# 1Sheeld_PLUS_REV3.net
KiCad netlist of a schematic drawn in EAGLE
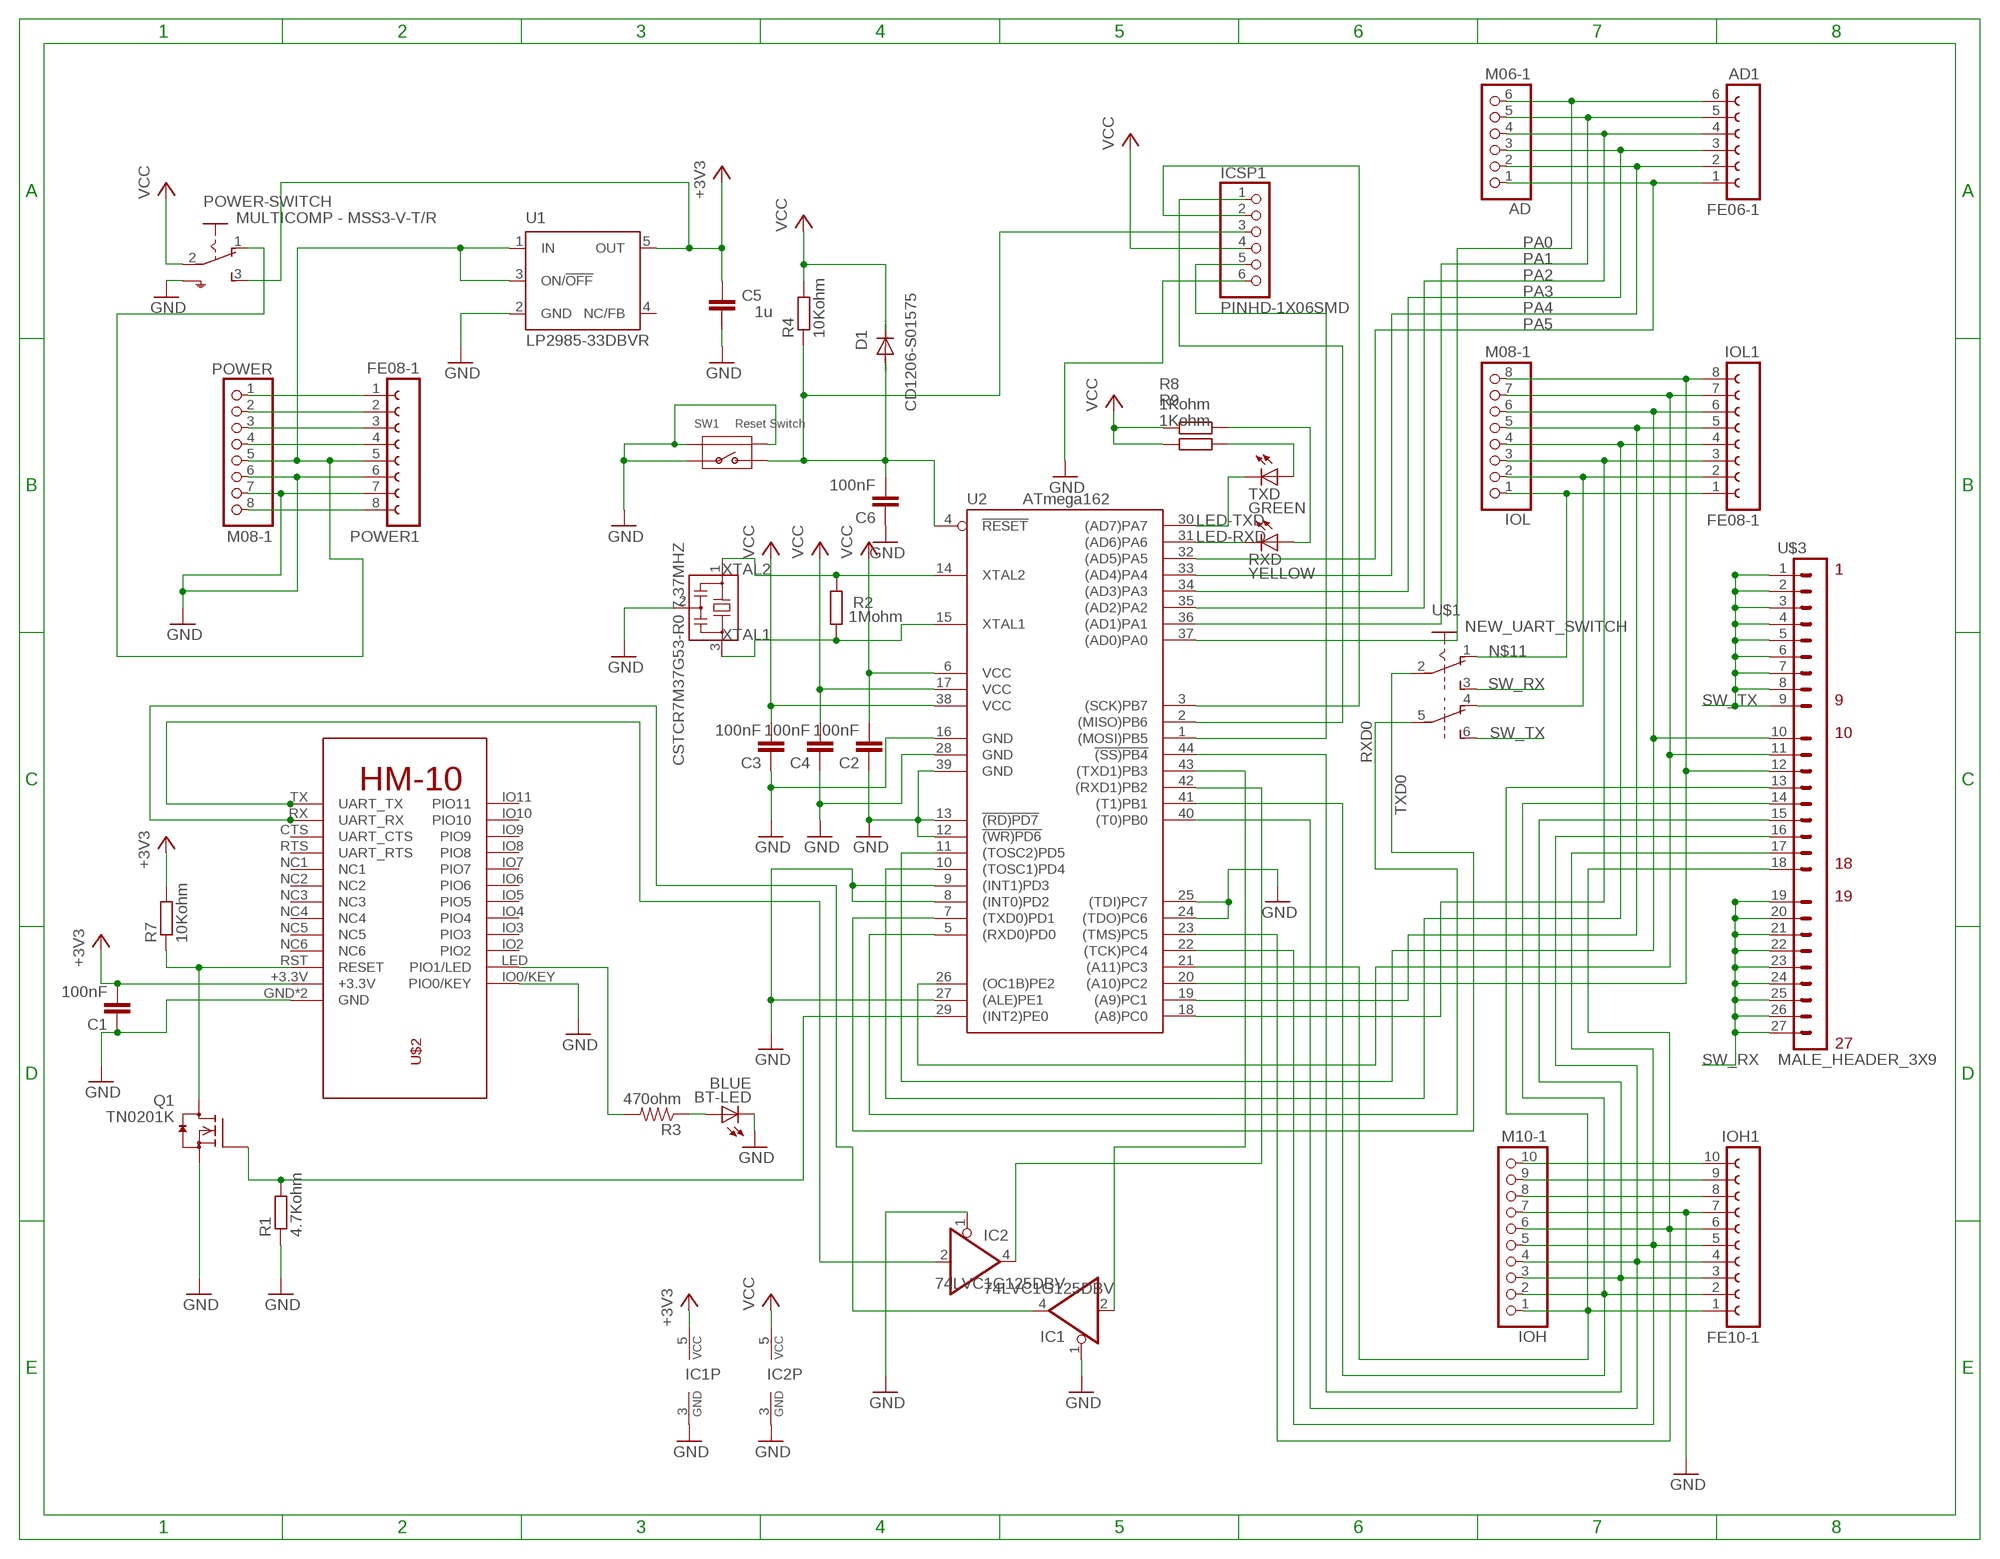
[diagram p0: schematic, sheet 1]

(export (version "E")
  (design (tool "Eeschema 10.0.6"))
  (components
    (comp (ref "AD")
      (value "M06-1")
      (footprint "eagle-import:1X06")
      (libsource (lib "eagle-import") (part "PINHD-1X6"))
    )
    (comp (ref "AD1")
      (value "FE06-1")
      (footprint "eagle-import:FE06")
      (libsource (lib "eagle-import") (part "FE06-1"))
    )
    (comp (ref "BT-LED")
      (value "BLUE")
      (footprint "eagle-import:CHIP-LED0805")
      (libsource (lib "eagle-import") (part "LEDCHIP-LED0805"))
    )
    (comp (ref "C1")
      (value "100nF")
      (footprint "eagle-import:C0603-ROUND")
      (libsource (lib "eagle-import") (part "C-EU0603-RND"))
    )
    (comp (ref "C2")
      (value "100nF")
      (footprint "eagle-import:C0603-ROUND")
      (libsource (lib "eagle-import") (part "C-EU0603-RND"))
    )
    (comp (ref "C3")
      (value "100nF")
      (footprint "eagle-import:C0603-ROUND")
      (libsource (lib "eagle-import") (part "C-EU0603-RND"))
    )
    (comp (ref "C4")
      (value "100nF")
      (footprint "eagle-import:C0603-ROUND")
      (libsource (lib "eagle-import") (part "C-EU0603-RND"))
    )
    (comp (ref "C5")
      (value "1u")
      (footprint "eagle-import:C0603-ROUND")
      (libsource (lib "eagle-import") (part "C-EU0603-RND"))
    )
    (comp (ref "C6")
      (value "100nF")
      (footprint "eagle-import:C0603-ROUND")
      (libsource (lib "eagle-import") (part "C-EU0603-RND"))
    )
    (comp (ref "D1")
      (value "CD1206-S01575")
      (footprint "eagle-import:MINIMELF")
      (libsource (lib "eagle-import") (part "DIODE-MINIMELF"))
    )
    (comp (ref "IC1")
      (value "74LVC1G125DBV")
      (footprint "eagle-import:SOT23-5")
      (libsource (lib "eagle-import") (part "741G125DBVLVC"))
    )
    (comp (ref "IC2")
      (value "74LVC1G125DBV")
      (footprint "eagle-import:SOT23-5")
      (libsource (lib "eagle-import") (part "741G125DBVLVC"))
    )
    (comp (ref "ICSP1")
      (value "PINHD-1X06SMD")
      (footprint "eagle-import:1X06_90SMD")
      (libsource (lib "eagle-import") (part "PINHD-1X06SMD"))
    )
    (comp (ref "IOH")
      (value "M10-1")
      (footprint "eagle-import:1X10")
      (libsource (lib "eagle-import") (part "PINHD-1X10_ARD"))
    )
    (comp (ref "IOH1")
      (value "FE10-1")
      (footprint "eagle-import:FE10")
      (libsource (lib "eagle-import") (part "FE10-1"))
    )
    (comp (ref "IOL")
      (value "M08-1")
      (footprint "eagle-import:1X08")
      (libsource (lib "eagle-import") (part "PINHD-1X8"))
    )
    (comp (ref "IOL1")
      (value "FE08-1")
      (footprint "eagle-import:FE08")
      (libsource (lib "eagle-import") (part "FE08-1"))
    )
    (comp (ref "POWER")
      (value "M08-1")
      (footprint "eagle-import:1X08")
      (libsource (lib "eagle-import") (part "PINHD-1X8"))
    )
    (comp (ref "POWER-SWITCH")
      (value "MULTICOMP - MSS3-V-T/R")
      (footprint "eagle-import:SWITCHMULTI")
      (libsource (lib "eagle-import") (part "SWITCHMULTI"))
    )
    (comp (ref "POWER1")
      (value "FE08-1")
      (footprint "eagle-import:FE08")
      (libsource (lib "eagle-import") (part "FE08-1"))
    )
    (comp (ref "Q1")
      (value "TN0201K")
      (footprint "eagle-import:SOT23")
      (libsource (lib "eagle-import") (part "TN0201K"))
    )
    (comp (ref "R1")
      (value "4.7Kohm")
      (footprint "eagle-import:M0805")
      (libsource (lib "eagle-import") (part "rcl_R-EU_M0805"))
    )
    (comp (ref "R2")
      (value "1Mohm")
      (footprint "eagle-import:R0603-ROUND")
      (libsource (lib "eagle-import") (part "R-EU_R0603"))
    )
    (comp (ref "R3")
      (value "470ohm")
      (footprint "eagle-import:0402-RES")
      (libsource (lib "eagle-import") (part "RESISTOR0402-RES"))
    )
    (comp (ref "R4")
      (value "10Kohm")
      (footprint "eagle-import:M0805")
      (libsource (lib "eagle-import") (part "rcl_R-EU_M0805"))
    )
    (comp (ref "R7")
      (value "10Kohm")
      (footprint "eagle-import:M0805")
      (libsource (lib "eagle-import") (part "rcl_R-EU_M0805"))
    )
    (comp (ref "R8")
      (value "1Kohm")
      (footprint "eagle-import:R0603-ROUND")
      (libsource (lib "eagle-import") (part "R-EU_R0603"))
    )
    (comp (ref "R9")
      (value "1Kohm")
      (footprint "eagle-import:R0603-ROUND")
      (libsource (lib "eagle-import") (part "R-EU_R0603"))
    )
    (comp (ref "RXD")
      (value "YELLOW")
      (footprint "eagle-import:CHIP-LED0805")
      (libsource (lib "eagle-import") (part "LEDCHIP-LED0805"))
    )
    (comp (ref "SW1")
      (value "Reset Switch")
      (footprint "eagle-import:DISCRETE_4P-SMD-7X3.5X3.5H")
      (libsource (lib "eagle-import") (part "DISCRETE_BUTTON-4P-REINFORCETS-1188E"))
    )
    (comp (ref "TXD")
      (value "GREEN")
      (footprint "eagle-import:CHIP-LED0805")
      (libsource (lib "eagle-import") (part "LEDCHIP-LED0805"))
    )
    (comp (ref "U$1")
      (value "NEW_UART_SWITCH")
      (footprint "eagle-import:NEW_UART_SWITCH")
      (libsource (lib "eagle-import") (part "NEW_UART_SWITCH"))
    )
    (comp (ref "U$2")
      (value "HM-10")
      (footprint "eagle-import:HM-10")
      (libsource (lib "eagle-import") (part "HM-10"))
    )
    (comp (ref "U$3")
      (value "MALE_HEADER_3X9")
      (footprint "eagle-import:MALE_HEADER_3X9")
      (libsource (lib "eagle-import") (part "MALE_HEADER_3X9"))
    )
    (comp (ref "U1")
      (value "LP2985-33DBVR")
      (footprint "eagle-import:SOT23-DBV")
      (libsource (lib "eagle-import") (part "LP2985-XXDBVR33"))
    )
    (comp (ref "U2")
      (value "ATmega162")
      (footprint "eagle-import:TQFP44")
      (libsource (lib "eagle-import") (part "ATMEGA162"))
    )
    (comp (ref "Y1")
      (value "CSTCR7M37G53-R0 7.37MHZ")
      (footprint "eagle-import:CSTCR6M")
      (fields (field (name "MPN") "CSTCR6M00G53-R0"))
      (libsource (lib "eagle-import") (part "CSTCR6M00G53Z"))
    )
  )
  (nets
    (net (code "1") (name "+3V3") (class "Default")
      (node (ref "C1") (pin "2") (pinfunction "2_2") (pintype "passive"))
      (node (ref "C5") (pin "2") (pinfunction "2_2") (pintype "passive"))
      (node (ref "IC1") (pin "5") (pinfunction "VCC_5") (pintype "power_in"))
      (node (ref "POWER-SWITCH") (pin "3") (pinfunction "S_3") (pintype "passive"))
      (node (ref "R7") (pin "2") (pinfunction "2_2") (pintype "passive"))
      (node (ref "U$2") (pin "+3.3V") (pinfunction "+3.3V_+3.3V") (pintype "bidirectional"))
      (node (ref "U1") (pin "5") (pinfunction "OUT_5") (pintype "passive"))
    )
    (net (code "2") (name "/LED-RXD") (class "Default")
      (node (ref "RXD") (pin "C") (pinfunction "C_C") (pintype "passive"))
      (node (ref "U2") (pin "31") (pinfunction "(AD6)PA6_31") (pintype "bidirectional"))
    )
    (net (code "3") (name "/LED-TXD") (class "Default")
      (node (ref "TXD") (pin "C") (pinfunction "C_C") (pintype "passive"))
      (node (ref "U2") (pin "30") (pinfunction "(AD7)PA7_30") (pintype "bidirectional"))
    )
    (net (code "4") (name "/N$11") (class "Default")
      (node (ref "IOL") (pin "1") (pinfunction "1_1") (pintype "passive"))
      (node (ref "IOL1") (pin "1") (pinfunction "1_1") (pintype "passive"))
      (node (ref "U$1") (pin "1") (pinfunction "1_1") (pintype "passive"))
    )
    (net (code "5") (name "/PA0") (class "Default")
      (node (ref "AD") (pin "6") (pinfunction "6_6") (pintype "passive"))
      (node (ref "AD1") (pin "6") (pinfunction "6_6") (pintype "passive"))
      (node (ref "U2") (pin "37") (pinfunction "(AD0)PA0_37") (pintype "bidirectional"))
    )
    (net (code "6") (name "/PA1") (class "Default")
      (node (ref "AD") (pin "5") (pinfunction "5_5") (pintype "passive"))
      (node (ref "AD1") (pin "5") (pinfunction "5_5") (pintype "passive"))
      (node (ref "U2") (pin "36") (pinfunction "(AD1)PA1_36") (pintype "bidirectional"))
    )
    (net (code "7") (name "/PA2") (class "Default")
      (node (ref "AD") (pin "4") (pinfunction "4_4") (pintype "passive"))
      (node (ref "AD1") (pin "4") (pinfunction "4_4") (pintype "passive"))
      (node (ref "U2") (pin "35") (pinfunction "(AD2)PA2_35") (pintype "bidirectional"))
    )
    (net (code "8") (name "/PA3") (class "Default")
      (node (ref "AD") (pin "3") (pinfunction "3_3") (pintype "passive"))
      (node (ref "AD1") (pin "3") (pinfunction "3_3") (pintype "passive"))
      (node (ref "U2") (pin "34") (pinfunction "(AD3)PA3_34") (pintype "bidirectional"))
    )
    (net (code "9") (name "/PA4") (class "Default")
      (node (ref "AD") (pin "2") (pinfunction "2_2") (pintype "passive"))
      (node (ref "AD1") (pin "2") (pinfunction "2_2") (pintype "passive"))
      (node (ref "U2") (pin "33") (pinfunction "(AD4)PA4_33") (pintype "bidirectional"))
    )
    (net (code "10") (name "/PA5") (class "Default")
      (node (ref "AD") (pin "1") (pinfunction "1_1") (pintype "passive"))
      (node (ref "AD1") (pin "1") (pinfunction "1_1") (pintype "passive"))
      (node (ref "U2") (pin "32") (pinfunction "(AD5)PA5_32") (pintype "bidirectional"))
    )
    (net (code "11") (name "/RXD0") (class "Default")
      (node (ref "U$1") (pin "5") (pinfunction "5_5") (pintype "passive"))
      (node (ref "U2") (pin "5") (pinfunction "(RXD0)PD0_5") (pintype "bidirectional"))
    )
    (net (code "12") (name "/SW_RX") (class "Default")
      (node (ref "U$1") (pin "3") (pinfunction "3_3") (pintype "passive"))
      (node (ref "U$3") (pin "19") (pinfunction "19_19") (pintype "passive"))
      (node (ref "U$3") (pin "20") (pinfunction "20_20") (pintype "passive"))
      (node (ref "U$3") (pin "21") (pinfunction "21_21") (pintype "passive"))
      (node (ref "U$3") (pin "22") (pinfunction "22_22") (pintype "passive"))
      (node (ref "U$3") (pin "23") (pinfunction "23_23") (pintype "passive"))
      (node (ref "U$3") (pin "24") (pinfunction "24_24") (pintype "passive"))
      (node (ref "U$3") (pin "25") (pinfunction "25_25") (pintype "passive"))
      (node (ref "U$3") (pin "26") (pinfunction "26_26") (pintype "passive"))
      (node (ref "U$3") (pin "27") (pinfunction "27_27") (pintype "passive"))
    )
    (net (code "13") (name "/SW_TX") (class "Default")
      (node (ref "U$1") (pin "6") (pinfunction "6_6") (pintype "passive"))
      (node (ref "U$3") (pin "1") (pinfunction "1_1") (pintype "passive"))
      (node (ref "U$3") (pin "2") (pinfunction "2_2") (pintype "passive"))
      (node (ref "U$3") (pin "3") (pinfunction "3_3") (pintype "passive"))
      (node (ref "U$3") (pin "4") (pinfunction "4_4") (pintype "passive"))
      (node (ref "U$3") (pin "5") (pinfunction "5_5") (pintype "passive"))
      (node (ref "U$3") (pin "6") (pinfunction "6_6") (pintype "passive"))
      (node (ref "U$3") (pin "7") (pinfunction "7_7") (pintype "passive"))
      (node (ref "U$3") (pin "8") (pinfunction "8_8") (pintype "passive"))
      (node (ref "U$3") (pin "9") (pinfunction "9_9") (pintype "passive"))
    )
    (net (code "14") (name "/TXD0") (class "Default")
      (node (ref "U$1") (pin "2") (pinfunction "2_2") (pintype "passive"))
      (node (ref "U2") (pin "7") (pinfunction "(TXD0)PD1_7") (pintype "bidirectional"))
    )
    (net (code "15") (name "/XTAL1") (class "Default")
      (node (ref "R2") (pin "1") (pinfunction "1_1") (pintype "passive"))
      (node (ref "U2") (pin "15") (pinfunction "XTAL1_15") (pintype "input"))
      (node (ref "Y1") (pin "3") (pinfunction "3_3") (pintype "passive"))
    )
    (net (code "16") (name "/XTAL2") (class "Default")
      (node (ref "R2") (pin "2") (pinfunction "2_2") (pintype "passive"))
      (node (ref "U2") (pin "14") (pinfunction "XTAL2_14") (pintype "input"))
      (node (ref "Y1") (pin "1") (pinfunction "1_1") (pintype "passive"))
    )
    (net (code "17") (name "GND") (class "Default")
      (node (ref "BT-LED") (pin "C") (pinfunction "C_C") (pintype "passive"))
      (node (ref "C1") (pin "1") (pinfunction "1_1") (pintype "passive"))
      (node (ref "C2") (pin "1") (pinfunction "1_1") (pintype "passive"))
      (node (ref "C3") (pin "1") (pinfunction "1_1") (pintype "passive"))
      (node (ref "C4") (pin "1") (pinfunction "1_1") (pintype "passive"))
      (node (ref "C5") (pin "1") (pinfunction "1_1") (pintype "passive"))
      (node (ref "C6") (pin "1") (pinfunction "1_1") (pintype "passive"))
      (node (ref "IC1") (pin "1") (pinfunction "OE_1") (pintype "input"))
      (node (ref "IC1") (pin "3") (pinfunction "GND_3") (pintype "power_in"))
      (node (ref "IC2") (pin "1") (pinfunction "OE_1") (pintype "input"))
      (node (ref "IC2") (pin "3") (pinfunction "GND_3") (pintype "power_in"))
      (node (ref "ICSP1") (pin "6") (pinfunction "6_6") (pintype "passive"))
      (node (ref "IOH") (pin "7") (pinfunction "7_7") (pintype "passive"))
      (node (ref "IOH1") (pin "7") (pinfunction "7_7") (pintype "passive"))
      (node (ref "POWER") (pin "6") (pinfunction "6_6") (pintype "passive"))
      (node (ref "POWER") (pin "7") (pinfunction "7_7") (pintype "passive"))
      (node (ref "POWER-SWITCH") (pin "P$4") (pinfunction "SH_P$4") (pintype "passive"))
      (node (ref "POWER-SWITCH") (pin "P$5") (pinfunction "SH_P$5") (pintype "passive"))
      (node (ref "POWER-SWITCH") (pin "P$6") (pinfunction "SH_P$6") (pintype "passive"))
      (node (ref "POWER-SWITCH") (pin "P$7") (pinfunction "SH_P$7") (pintype "passive"))
      (node (ref "POWER1") (pin "6") (pinfunction "6_6") (pintype "passive"))
      (node (ref "POWER1") (pin "7") (pinfunction "7_7") (pintype "passive"))
      (node (ref "Q1") (pin "2") (pinfunction "S_2") (pintype "passive"))
      (node (ref "R1") (pin "1") (pinfunction "1_1") (pintype "passive"))
      (node (ref "SW1") (pin "1") (pinfunction "1_1") (pintype "bidirectional"))
      (node (ref "SW1") (pin "S1") (pinfunction "S1_S1") (pintype "bidirectional"))
      (node (ref "SW1") (pin "S2") (pinfunction "S2_S2") (pintype "bidirectional"))
      (node (ref "U$2") (pin "GND") (pinfunction "GND_GND") (pintype "bidirectional"))
      (node (ref "U$2") (pin "GND2") (pinfunction "GND_GND2") (pintype "bidirectional"))
      (node (ref "U$2") (pin "IO0/KEY") (pinfunction "PIO0/KEY_IO0/KEY") (pintype "bidirectional"))
      (node (ref "U1") (pin "2") (pinfunction "GND_2") (pintype "power_in"))
      (node (ref "U2") (pin "12") (pinfunction "~{(WR})PD6_12") (pintype "bidirectional"))
      (node (ref "U2") (pin "13") (pinfunction "~{(RD})PD7_13") (pintype "bidirectional"))
      (node (ref "U2") (pin "16") (pinfunction "GND_16") (pintype "power_in"))
      (node (ref "U2") (pin "24") (pinfunction "(TDO)PC6_24") (pintype "bidirectional"))
      (node (ref "U2") (pin "25") (pinfunction "(TDI)PC7_25") (pintype "bidirectional"))
      (node (ref "U2") (pin "27") (pinfunction "(ALE)PE1_27") (pintype "bidirectional"))
      (node (ref "U2") (pin "28") (pinfunction "GND_28") (pintype "power_in"))
      (node (ref "U2") (pin "39") (pinfunction "GND_39") (pintype "power_in"))
      (node (ref "U2") (pin "8") (pinfunction "(INT0)PD2_8") (pintype "bidirectional"))
      (node (ref "U2") (pin "9") (pinfunction "(INT1)PD3_9") (pintype "bidirectional"))
      (node (ref "Y1") (pin "2") (pinfunction "2_2") (pintype "passive"))
    )
    (net (code "18") (name "Net-(BT-LED-PadA)") (class "Default")
      (node (ref "BT-LED") (pin "A") (pinfunction "A_A") (pintype "passive"))
      (node (ref "R3") (pin "1") (pinfunction "1_1") (pintype "passive"))
    )
    (net (code "19") (name "Net-(IC1A-I)") (class "Default")
      (node (ref "IC1") (pin "2") (pinfunction "I_2") (pintype "input"))
      (node (ref "U2") (pin "43") (pinfunction "(TXD1)PB3_43") (pintype "bidirectional"))
    )
    (net (code "20") (name "Net-(IC1A-O)") (class "Default")
      (node (ref "IC1") (pin "4") (pinfunction "O_4") (pintype "tri_state"))
      (node (ref "U$2") (pin "RX") (pinfunction "UART_RX_RX") (pintype "bidirectional"))
    )
    (net (code "21") (name "Net-(IC2A-I)") (class "Default")
      (node (ref "IC2") (pin "2") (pinfunction "I_2") (pintype "input"))
      (node (ref "U$2") (pin "TX") (pinfunction "UART_TX_TX") (pintype "bidirectional"))
    )
    (net (code "22") (name "Net-(IC2A-O)") (class "Default")
      (node (ref "IC2") (pin "4") (pinfunction "O_4") (pintype "tri_state"))
      (node (ref "U2") (pin "42") (pinfunction "(RXD1)PB2_42") (pintype "bidirectional"))
    )
    (net (code "23") (name "Net-(IOH-Pad8)") (class "Default")
      (node (ref "IOH") (pin "8") (pinfunction "8_8") (pintype "passive"))
      (node (ref "IOH1") (pin "8") (pinfunction "8_8") (pintype "passive"))
    )
    (net (code "24") (name "Net-(IOH-Pad9)") (class "Default")
      (node (ref "IOH") (pin "9") (pinfunction "9_9") (pintype "passive"))
      (node (ref "IOH1") (pin "9") (pinfunction "9_9") (pintype "passive"))
    )
    (net (code "25") (name "Net-(IOH-Pad10)") (class "Default")
      (node (ref "IOH") (pin "10") (pinfunction "10_10") (pintype "passive"))
      (node (ref "IOH1") (pin "10") (pinfunction "10_10") (pintype "passive"))
    )
    (net (code "26") (name "Net-(IOL-Pad2)") (class "Default")
      (node (ref "IOL") (pin "2") (pinfunction "2_2") (pintype "passive"))
      (node (ref "IOL1") (pin "2") (pinfunction "2_2") (pintype "passive"))
      (node (ref "U$1") (pin "4") (pinfunction "4_4") (pintype "passive"))
    )
    (net (code "27") (name "Net-(POWER-Pad1)") (class "Default")
      (node (ref "POWER") (pin "1") (pinfunction "1_1") (pintype "passive"))
      (node (ref "POWER1") (pin "1") (pinfunction "1_1") (pintype "passive"))
    )
    (net (code "28") (name "Net-(POWER-Pad2)") (class "Default")
      (node (ref "POWER") (pin "2") (pinfunction "2_2") (pintype "passive"))
      (node (ref "POWER1") (pin "2") (pinfunction "2_2") (pintype "passive"))
    )
    (net (code "29") (name "Net-(POWER-Pad3)") (class "Default")
      (node (ref "POWER") (pin "3") (pinfunction "3_3") (pintype "passive"))
      (node (ref "POWER1") (pin "3") (pinfunction "3_3") (pintype "passive"))
    )
    (net (code "30") (name "Net-(POWER-Pad4)") (class "Default")
      (node (ref "POWER") (pin "4") (pinfunction "4_4") (pintype "passive"))
      (node (ref "POWER1") (pin "4") (pinfunction "4_4") (pintype "passive"))
    )
    (net (code "31") (name "Net-(POWER-Pad8)") (class "Default")
      (node (ref "POWER") (pin "8") (pinfunction "8_8") (pintype "passive"))
      (node (ref "POWER1") (pin "8") (pinfunction "8_8") (pintype "passive"))
    )
    (net (code "32") (name "Net-(POWER-SWITCH-O)") (class "Default")
      (node (ref "POWER") (pin "5") (pinfunction "5_5") (pintype "passive"))
      (node (ref "POWER-SWITCH") (pin "1") (pinfunction "O_1") (pintype "passive"))
      (node (ref "POWER1") (pin "5") (pinfunction "5_5") (pintype "passive"))
      (node (ref "U1") (pin "1") (pinfunction "IN_1") (pintype "input"))
      (node (ref "U1") (pin "3") (pinfunction "ON/~{OFF}_3") (pintype "input"))
    )
    (net (code "33") (name "Net-(Q1-D)") (class "Default")
      (node (ref "Q1") (pin "3") (pinfunction "D_3") (pintype "passive"))
      (node (ref "R7") (pin "1") (pinfunction "1_1") (pintype "passive"))
      (node (ref "U$2") (pin "RST") (pinfunction "RESET_RST") (pintype "bidirectional"))
    )
    (net (code "34") (name "Net-(Q1-G)") (class "Default")
      (node (ref "Q1") (pin "1") (pinfunction "G_1") (pintype "passive"))
      (node (ref "R1") (pin "2") (pinfunction "2_2") (pintype "passive"))
      (node (ref "U2") (pin "29") (pinfunction "(INT2)PE0_29") (pintype "bidirectional"))
    )
    (net (code "35") (name "Net-(R8-Pad1)") (class "Default")
      (node (ref "R8") (pin "1") (pinfunction "1_1") (pintype "passive"))
      (node (ref "RXD") (pin "A") (pinfunction "A_A") (pintype "passive"))
    )
    (net (code "36") (name "Net-(R9-Pad1)") (class "Default")
      (node (ref "R9") (pin "1") (pinfunction "1_1") (pintype "passive"))
      (node (ref "TXD") (pin "A") (pinfunction "A_A") (pintype "passive"))
    )
    (net (code "37") (name "Net-(U$2-PIO1{slash}LED)") (class "Default")
      (node (ref "R3") (pin "2") (pinfunction "2_2") (pintype "passive"))
      (node (ref "U$2") (pin "LED") (pinfunction "PIO1/LED_LED") (pintype "bidirectional"))
    )
    (net (code "38") (name "Net-(U2-(A8)PC0)") (class "Default")
      (node (ref "IOL") (pin "3") (pinfunction "3_3") (pintype "passive"))
      (node (ref "IOL1") (pin "3") (pinfunction "3_3") (pintype "passive"))
      (node (ref "U2") (pin "18") (pinfunction "(A8)PC0_18") (pintype "bidirectional"))
    )
    (net (code "39") (name "Net-(U2-(A9)PC1)") (class "Default")
      (node (ref "IOL") (pin "5") (pinfunction "5_5") (pintype "passive"))
      (node (ref "IOL1") (pin "5") (pinfunction "5_5") (pintype "passive"))
      (node (ref "U2") (pin "19") (pinfunction "(A9)PC1_19") (pintype "bidirectional"))
    )
    (net (code "40") (name "Net-(U2-(A10)PC2)") (class "Default")
      (node (ref "IOL") (pin "8") (pinfunction "8_8") (pintype "passive"))
      (node (ref "IOL1") (pin "8") (pinfunction "8_8") (pintype "passive"))
      (node (ref "U$3") (pin "12") (pinfunction "12_12") (pintype "passive"))
      (node (ref "U2") (pin "20") (pinfunction "(A10)PC2_20") (pintype "bidirectional"))
    )
    (net (code "41") (name "Net-(U2-(A11)PC3)") (class "Default")
      (node (ref "IOH") (pin "1") (pinfunction "1_1") (pintype "passive"))
      (node (ref "IOH1") (pin "1") (pinfunction "1_1") (pintype "passive"))
      (node (ref "U$3") (pin "13") (pinfunction "13_13") (pintype "passive"))
      (node (ref "U2") (pin "21") (pinfunction "(A11)PC3_21") (pintype "bidirectional"))
    )
    (net (code "42") (name "Net-(U2-(MISO)PB6)") (class "Default")
      (node (ref "ICSP1") (pin "1") (pinfunction "1_1") (pintype "passive"))
      (node (ref "U2") (pin "2") (pinfunction "(MISO)PB6_2") (pintype "bidirectional"))
    )
    (net (code "43") (name "Net-(U2-(MOSI)PB5)") (class "Default")
      (node (ref "ICSP1") (pin "5") (pinfunction "5_5") (pintype "passive"))
      (node (ref "U2") (pin "1") (pinfunction "(MOSI)PB5_1") (pintype "bidirectional"))
    )
    (net (code "44") (name "Net-(U2-(OC1B)PE2)") (class "Default")
      (node (ref "IOL") (pin "7") (pinfunction "7_7") (pintype "passive"))
      (node (ref "IOL1") (pin "7") (pinfunction "7_7") (pintype "passive"))
      (node (ref "U$3") (pin "11") (pinfunction "11_11") (pintype "passive"))
      (node (ref "U2") (pin "26") (pinfunction "(OC1B)PE2_26") (pintype "bidirectional"))
    )
    (net (code "45") (name "Net-(U2-(SCK)PB7)") (class "Default")
      (node (ref "ICSP1") (pin "2") (pinfunction "2_2") (pintype "passive"))
      (node (ref "U2") (pin "3") (pinfunction "(SCK)PB7_3") (pintype "bidirectional"))
    )
    (net (code "46") (name "Net-(U2-(T0)PB0)") (class "Default")
      (node (ref "IOH") (pin "4") (pinfunction "4_4") (pintype "passive"))
      (node (ref "IOH1") (pin "4") (pinfunction "4_4") (pintype "passive"))
      (node (ref "U$3") (pin "16") (pinfunction "16_16") (pintype "passive"))
      (node (ref "U2") (pin "40") (pinfunction "(T0)PB0_40") (pintype "bidirectional"))
    )
    (net (code "47") (name "Net-(U2-(T1)PB1)") (class "Default")
      (node (ref "IOH") (pin "2") (pinfunction "2_2") (pintype "passive"))
      (node (ref "IOH1") (pin "2") (pinfunction "2_2") (pintype "passive"))
      (node (ref "U$3") (pin "14") (pinfunction "14_14") (pintype "passive"))
      (node (ref "U2") (pin "41") (pinfunction "(T1)PB1_41") (pintype "bidirectional"))
    )
    (net (code "48") (name "Net-(U2-(TCK)PC4)") (class "Default")
      (node (ref "IOH") (pin "5") (pinfunction "5_5") (pintype "passive"))
      (node (ref "IOH1") (pin "5") (pinfunction "5_5") (pintype "passive"))
      (node (ref "U$3") (pin "17") (pinfunction "17_17") (pintype "passive"))
      (node (ref "U2") (pin "22") (pinfunction "(TCK)PC4_22") (pintype "bidirectional"))
    )
    (net (code "49") (name "Net-(U2-(TMS)PC5)") (class "Default")
      (node (ref "IOH") (pin "6") (pinfunction "6_6") (pintype "passive"))
      (node (ref "IOH1") (pin "6") (pinfunction "6_6") (pintype "passive"))
      (node (ref "U$3") (pin "18") (pinfunction "18_18") (pintype "passive"))
      (node (ref "U2") (pin "23") (pinfunction "(TMS)PC5_23") (pintype "bidirectional"))
    )
    (net (code "50") (name "Net-(U2-(TOSC1)PD4)") (class "Default")
      (node (ref "IOL") (pin "4") (pinfunction "4_4") (pintype "passive"))
      (node (ref "IOL1") (pin "4") (pinfunction "4_4") (pintype "passive"))
      (node (ref "U2") (pin "10") (pinfunction "(TOSC1)PD4_10") (pintype "bidirectional"))
    )
    (net (code "51") (name "Net-(U2-(TOSC2)PD5)") (class "Default")
      (node (ref "IOL") (pin "6") (pinfunction "6_6") (pintype "passive"))
      (node (ref "IOL1") (pin "6") (pinfunction "6_6") (pintype "passive"))
      (node (ref "U$3") (pin "10") (pinfunction "10_10") (pintype "passive"))
      (node (ref "U2") (pin "11") (pinfunction "(TOSC2)PD5_11") (pintype "bidirectional"))
    )
    (net (code "52") (name "Net-(U2-~{(SS})PB4)") (class "Default")
      (node (ref "IOH") (pin "3") (pinfunction "3_3") (pintype "passive"))
      (node (ref "IOH1") (pin "3") (pinfunction "3_3") (pintype "passive"))
      (node (ref "U$3") (pin "15") (pinfunction "15_15") (pintype "passive"))
      (node (ref "U2") (pin "44") (pinfunction "~{(SS})PB4_44") (pintype "bidirectional"))
    )
    (net (code "53") (name "Net-(U2-~{RESET})") (class "Default")
      (node (ref "C6") (pin "2") (pinfunction "2_2") (pintype "passive"))
      (node (ref "D1") (pin "A") (pinfunction "A_A") (pintype "passive"))
      (node (ref "ICSP1") (pin "3") (pinfunction "3_3") (pintype "passive"))
      (node (ref "R4") (pin "1") (pinfunction "1_1") (pintype "passive"))
      (node (ref "SW1") (pin "2") (pinfunction "2_2") (pintype "bidirectional"))
      (node (ref "U2") (pin "4") (pinfunction "~{RESET}_4") (pintype "input"))
    )
    (net (code "54") (name "VCC") (class "Default")
      (node (ref "C2") (pin "2") (pinfunction "2_2") (pintype "passive"))
      (node (ref "C3") (pin "2") (pinfunction "2_2") (pintype "passive"))
      (node (ref "C4") (pin "2") (pinfunction "2_2") (pintype "passive"))
      (node (ref "D1") (pin "C") (pinfunction "C_C") (pintype "passive"))
      (node (ref "IC2") (pin "5") (pinfunction "VCC_5") (pintype "power_in"))
      (node (ref "ICSP1") (pin "4") (pinfunction "4_4") (pintype "passive"))
      (node (ref "POWER-SWITCH") (pin "2") (pinfunction "P_2") (pintype "passive"))
      (node (ref "R4") (pin "2") (pinfunction "2_2") (pintype "passive"))
      (node (ref "R8") (pin "2") (pinfunction "2_2") (pintype "passive"))
      (node (ref "R9") (pin "2") (pinfunction "2_2") (pintype "passive"))
      (node (ref "U2") (pin "17") (pinfunction "VCC_17") (pintype "power_in"))
      (node (ref "U2") (pin "38") (pinfunction "VCC_38") (pintype "power_in"))
      (node (ref "U2") (pin "6") (pinfunction "VCC_6") (pintype "power_in"))
    )
    (net (code "55") (name "unconnected-(U$2-PIO2-PadIO2)") (class "Default")
      (node (ref "U$2") (pin "IO2") (pinfunction "PIO2_IO2") (pintype "bidirectional"))
    )
    (net (code "56") (name "unconnected-(U$2-PIO3-PadIO3)") (class "Default")
      (node (ref "U$2") (pin "IO3") (pinfunction "PIO3_IO3") (pintype "bidirectional"))
    )
    (net (code "57") (name "unconnected-(U$2-PIO4-PadIO4)") (class "Default")
      (node (ref "U$2") (pin "IO4") (pinfunction "PIO4_IO4") (pintype "bidirectional"))
    )
    (net (code "58") (name "unconnected-(U$2-PIO5-PadIO5)") (class "Default")
      (node (ref "U$2") (pin "IO5") (pinfunction "PIO5_IO5") (pintype "bidirectional"))
    )
    (net (code "59") (name "unconnected-(U$2-PIO6-PadIO6)") (class "Default")
      (node (ref "U$2") (pin "IO6") (pinfunction "PIO6_IO6") (pintype "bidirectional"))
    )
    (net (code "60") (name "unconnected-(U$2-PIO7-PadIO7)") (class "Default")
      (node (ref "U$2") (pin "IO7") (pinfunction "PIO7_IO7") (pintype "bidirectional"))
    )
    (net (code "61") (name "unconnected-(U$2-PIO8-PadIO8)") (class "Default")
      (node (ref "U$2") (pin "IO8") (pinfunction "PIO8_IO8") (pintype "bidirectional"))
    )
    (net (code "62") (name "unconnected-(U$2-PIO9-PadIO9)") (class "Default")
      (node (ref "U$2") (pin "IO9") (pinfunction "PIO9_IO9") (pintype "bidirectional"))
    )
    (net (code "63") (name "unconnected-(U$2-PIO10-PadIO10)") (class "Default")
      (node (ref "U$2") (pin "IO10") (pinfunction "PIO10_IO10") (pintype "bidirectional"))
    )
    (net (code "64") (name "unconnected-(U$2-PIO11-PadIO11)") (class "Default")
      (node (ref "U$2") (pin "IO11") (pinfunction "PIO11_IO11") (pintype "bidirectional"))
    )
    (net (code "65") (name "unconnected-(U$2-PadNC1)") (class "Default")
      (node (ref "U$2") (pin "NC1") (pinfunction "NC1_NC1") (pintype "bidirectional"))
    )
    (net (code "66") (name "unconnected-(U$2-PadNC2)") (class "Default")
      (node (ref "U$2") (pin "NC2") (pinfunction "NC2_NC2") (pintype "bidirectional"))
    )
    (net (code "67") (name "unconnected-(U$2-PadNC3)") (class "Default")
      (node (ref "U$2") (pin "NC3") (pinfunction "NC3_NC3") (pintype "bidirectional"))
    )
    (net (code "68") (name "unconnected-(U$2-PadNC4)") (class "Default")
      (node (ref "U$2") (pin "NC4") (pinfunction "NC4_NC4") (pintype "bidirectional"))
    )
    (net (code "69") (name "unconnected-(U$2-PadNC5)") (class "Default")
      (node (ref "U$2") (pin "NC5") (pinfunction "NC5_NC5") (pintype "bidirectional"))
    )
    (net (code "70") (name "unconnected-(U$2-PadNC6)") (class "Default")
      (node (ref "U$2") (pin "NC6") (pinfunction "NC6_NC6") (pintype "bidirectional"))
    )
    (net (code "71") (name "unconnected-(U$2-UART_CTS-PadCTS)") (class "Default")
      (node (ref "U$2") (pin "CTS") (pinfunction "UART_CTS_CTS") (pintype "bidirectional"))
    )
    (net (code "72") (name "unconnected-(U$2-UART_RTS-PadRTS)") (class "Default")
      (node (ref "U$2") (pin "RTS") (pinfunction "UART_RTS_RTS") (pintype "bidirectional"))
    )
    (net (code "73") (name "unconnected-(U1-NC{slash}FB-Pad4)") (class "Default")
      (node (ref "U1") (pin "4") (pinfunction "NC/FB_4") (pintype "passive"))
    )
  )
)
